# part_1.net
KiCad netlist of a schematic drawn in EAGLE
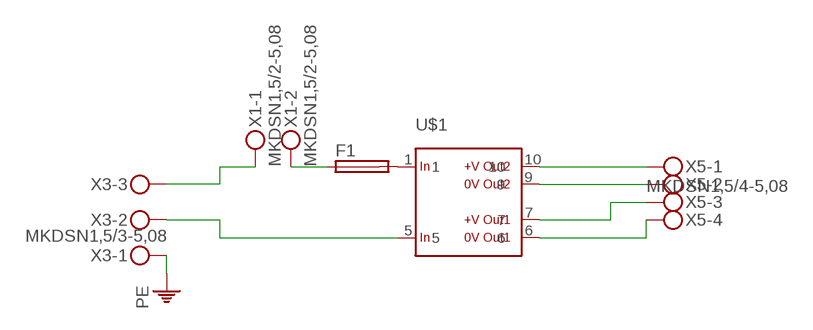
[diagram p0: schematic, sheet 1]

(export (version "E")
  (design (tool "Eeschema 10.0.6"))
  (components
    (comp (ref "F1")
      (value "SH22,5A")
      (footprint "eagle-import:SH22,5A")
      (fields (field (name "MPN") "0031.7701.11"))
      (libsource (lib "eagle-import") (part "SH22,5A"))
    )
    (comp (ref "U$1")
      (value "DOUBLE_ISO")
      (footprint "eagle-import:2ISO")
      (libsource (lib "eagle-import") (part "DOUBLE_ISO"))
    )
    (comp (ref "X1")
      (value "MKDSN1,5/2-5,08")
      (footprint "eagle-import:MKDSN1,5_2-5,08")
      (libsource (lib "eagle-import") (part "MKDSN1,5/2-5,08"))
    )
    (comp (ref "X3")
      (value "MKDSN1,5/3-5,08")
      (footprint "eagle-import:MKDSN1,5_3-5,08")
      (libsource (lib "eagle-import") (part "MKDSN1,5/3-5,08"))
    )
    (comp (ref "X5")
      (value "MKDSN1,5/4-5,08")
      (footprint "eagle-import:MKDSN1,5_4-5,08")
      (libsource (lib "eagle-import") (part "MKDSN1,5/4-5,08"))
    )
  )
  (nets
    (net (code "1") (name "Net-(F1-Pad2)") (class "Default")
      (node (ref "F1") (pin "2") (pinfunction "2_2") (pintype "passive"))
      (node (ref "U$1") (pin "1") (pinfunction "1_1") (pintype "input"))
    )
    (net (code "2") (name "Net-(X1A-KL)") (class "Default")
      (node (ref "X1") (pin "1") (pinfunction "KL_1") (pintype "passive"))
      (node (ref "X3") (pin "3") (pinfunction "KL_3") (pintype "passive"))
    )
    (net (code "3") (name "Net-(X1B-KL)") (class "Default")
      (node (ref "F1") (pin "1") (pinfunction "1_1") (pintype "passive"))
      (node (ref "X1") (pin "2") (pinfunction "KL_2") (pintype "passive"))
    )
    (net (code "4") (name "Net-(X3B-KL)") (class "Default")
      (node (ref "U$1") (pin "5") (pinfunction "5_5") (pintype "input"))
      (node (ref "X3") (pin "2") (pinfunction "KL_2") (pintype "passive"))
    )
    (net (code "5") (name "Net-(X5A-KL)") (class "Default")
      (node (ref "U$1") (pin "10") (pinfunction "10_10") (pintype "output"))
      (node (ref "X5") (pin "1") (pinfunction "KL_1") (pintype "passive"))
    )
    (net (code "6") (name "Net-(X5B-KL)") (class "Default")
      (node (ref "U$1") (pin "9") (pinfunction "9_9") (pintype "output"))
      (node (ref "X5") (pin "2") (pinfunction "KL_2") (pintype "passive"))
    )
    (net (code "7") (name "Net-(X5C-KL)") (class "Default")
      (node (ref "U$1") (pin "7") (pinfunction "7_7") (pintype "output"))
      (node (ref "X5") (pin "3") (pinfunction "KL_3") (pintype "passive"))
    )
    (net (code "8") (name "Net-(X5D-KL)") (class "Default")
      (node (ref "U$1") (pin "6") (pinfunction "6_6") (pintype "output"))
      (node (ref "X5") (pin "4") (pinfunction "KL_4") (pintype "passive"))
    )
    (net (code "9") (name "PE") (class "Default")
      (node (ref "X3") (pin "1") (pinfunction "KL_1") (pintype "passive"))
    )
  )
)
